# W025A.net
KiCad netlist of a schematic drawn in EAGLE
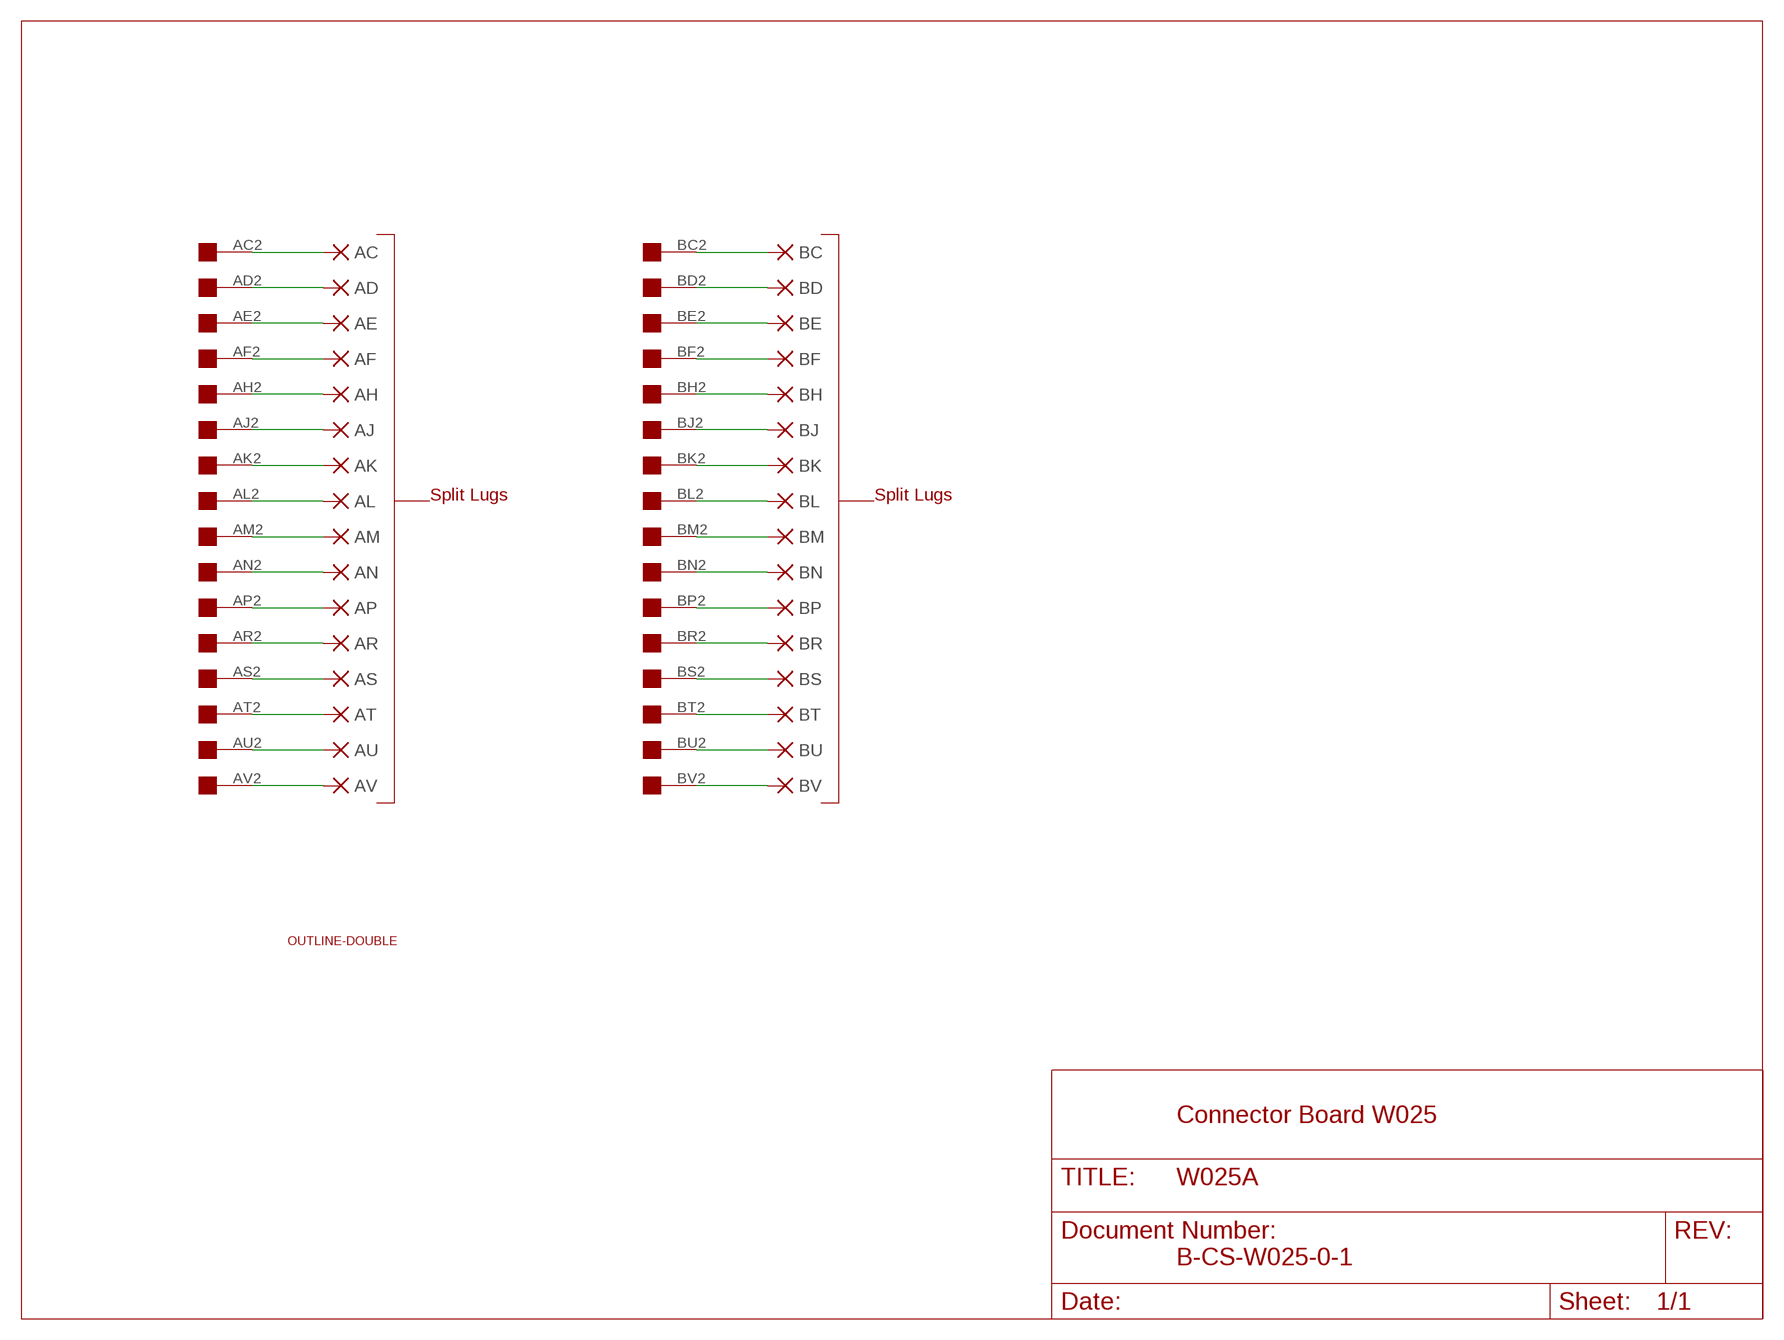
[diagram p0: schematic, sheet 1]

(export (version "E")
  (design (tool "Eeschema 10.0.6"))
  (components
    (comp (ref "AC")
      (value "PAD-0465")
      (footprint "eagle-import:0465")
      (libsource (lib "eagle-import") (part "PAD-0465"))
    )
    (comp (ref "AD")
      (value "PAD-0465")
      (footprint "eagle-import:0465")
      (libsource (lib "eagle-import") (part "PAD-0465"))
    )
    (comp (ref "AE")
      (value "PAD-0465")
      (footprint "eagle-import:0465")
      (libsource (lib "eagle-import") (part "PAD-0465"))
    )
    (comp (ref "AF")
      (value "PAD-0465")
      (footprint "eagle-import:0465")
      (libsource (lib "eagle-import") (part "PAD-0465"))
    )
    (comp (ref "AH")
      (value "PAD-0465")
      (footprint "eagle-import:0465")
      (libsource (lib "eagle-import") (part "PAD-0465"))
    )
    (comp (ref "AJ")
      (value "PAD-0465")
      (footprint "eagle-import:0465")
      (libsource (lib "eagle-import") (part "PAD-0465"))
    )
    (comp (ref "AK")
      (value "PAD-0465")
      (footprint "eagle-import:0465")
      (libsource (lib "eagle-import") (part "PAD-0465"))
    )
    (comp (ref "AL")
      (value "PAD-0465")
      (footprint "eagle-import:0465")
      (libsource (lib "eagle-import") (part "PAD-0465"))
    )
    (comp (ref "AM")
      (value "PAD-0465")
      (footprint "eagle-import:0465")
      (libsource (lib "eagle-import") (part "PAD-0465"))
    )
    (comp (ref "AN")
      (value "PAD-0465")
      (footprint "eagle-import:0465")
      (libsource (lib "eagle-import") (part "PAD-0465"))
    )
    (comp (ref "AP")
      (value "PAD-0465")
      (footprint "eagle-import:0465")
      (libsource (lib "eagle-import") (part "PAD-0465"))
    )
    (comp (ref "AR")
      (value "PAD-0465")
      (footprint "eagle-import:0465")
      (libsource (lib "eagle-import") (part "PAD-0465"))
    )
    (comp (ref "AS")
      (value "PAD-0465")
      (footprint "eagle-import:0465")
      (libsource (lib "eagle-import") (part "PAD-0465"))
    )
    (comp (ref "AT")
      (value "PAD-0465")
      (footprint "eagle-import:0465")
      (libsource (lib "eagle-import") (part "PAD-0465"))
    )
    (comp (ref "AU")
      (value "PAD-0465")
      (footprint "eagle-import:0465")
      (libsource (lib "eagle-import") (part "PAD-0465"))
    )
    (comp (ref "AV")
      (value "PAD-0465")
      (footprint "eagle-import:0465")
      (libsource (lib "eagle-import") (part "PAD-0465"))
    )
    (comp (ref "BC")
      (value "PAD-0465")
      (footprint "eagle-import:0465")
      (libsource (lib "eagle-import") (part "PAD-0465"))
    )
    (comp (ref "BD")
      (value "PAD-0465")
      (footprint "eagle-import:0465")
      (libsource (lib "eagle-import") (part "PAD-0465"))
    )
    (comp (ref "BE")
      (value "PAD-0465")
      (footprint "eagle-import:0465")
      (libsource (lib "eagle-import") (part "PAD-0465"))
    )
    (comp (ref "BF")
      (value "PAD-0465")
      (footprint "eagle-import:0465")
      (libsource (lib "eagle-import") (part "PAD-0465"))
    )
    (comp (ref "BH")
      (value "PAD-0465")
      (footprint "eagle-import:0465")
      (libsource (lib "eagle-import") (part "PAD-0465"))
    )
    (comp (ref "BJ")
      (value "PAD-0465")
      (footprint "eagle-import:0465")
      (libsource (lib "eagle-import") (part "PAD-0465"))
    )
    (comp (ref "BK")
      (value "PAD-0465")
      (footprint "eagle-import:0465")
      (libsource (lib "eagle-import") (part "PAD-0465"))
    )
    (comp (ref "BL")
      (value "PAD-0465")
      (footprint "eagle-import:0465")
      (libsource (lib "eagle-import") (part "PAD-0465"))
    )
    (comp (ref "BM")
      (value "PAD-0465")
      (footprint "eagle-import:0465")
      (libsource (lib "eagle-import") (part "PAD-0465"))
    )
    (comp (ref "BN")
      (value "PAD-0465")
      (footprint "eagle-import:0465")
      (libsource (lib "eagle-import") (part "PAD-0465"))
    )
    (comp (ref "BP")
      (value "PAD-0465")
      (footprint "eagle-import:0465")
      (libsource (lib "eagle-import") (part "PAD-0465"))
    )
    (comp (ref "BR")
      (value "PAD-0465")
      (footprint "eagle-import:0465")
      (libsource (lib "eagle-import") (part "PAD-0465"))
    )
    (comp (ref "BS")
      (value "PAD-0465")
      (footprint "eagle-import:0465")
      (libsource (lib "eagle-import") (part "PAD-0465"))
    )
    (comp (ref "BT")
      (value "PAD-0465")
      (footprint "eagle-import:0465")
      (libsource (lib "eagle-import") (part "PAD-0465"))
    )
    (comp (ref "BU")
      (value "PAD-0465")
      (footprint "eagle-import:0465")
      (libsource (lib "eagle-import") (part "PAD-0465"))
    )
    (comp (ref "BV")
      (value "PAD-0465")
      (footprint "eagle-import:0465")
      (libsource (lib "eagle-import") (part "PAD-0465"))
    )
    (comp (ref "U$1")
      (value "OUTLINE-DOUBLE")
      (footprint "eagle-import:DOUBLE")
      (libsource (lib "eagle-import") (part "OUTLINE-DOUBLE"))
    )
    (comp (ref "U$3")
      (value "DOUBLE")
      (footprint "eagle-import:EDGE-CON4")
      (libsource (lib "eagle-import") (part "DOUBLE"))
    )
  )
  (nets
    (net (code "1") (name "Net-(AC-P)") (class "Default")
      (node (ref "AC") (pin "P$1") (pinfunction "P_P$1") (pintype "passive"))
      (node (ref "U$3") (pin "AC2") (pinfunction "1_AC2") (pintype "bidirectional"))
    )
    (net (code "2") (name "Net-(AD-P)") (class "Default")
      (node (ref "AD") (pin "P$1") (pinfunction "P_P$1") (pintype "passive"))
      (node (ref "U$3") (pin "AD2") (pinfunction "1_AD2") (pintype "bidirectional"))
    )
    (net (code "3") (name "Net-(AE-P)") (class "Default")
      (node (ref "AE") (pin "P$1") (pinfunction "P_P$1") (pintype "passive"))
      (node (ref "U$3") (pin "AE2") (pinfunction "1_AE2") (pintype "bidirectional"))
    )
    (net (code "4") (name "Net-(AF-P)") (class "Default")
      (node (ref "AF") (pin "P$1") (pinfunction "P_P$1") (pintype "passive"))
      (node (ref "U$3") (pin "AF2") (pinfunction "1_AF2") (pintype "bidirectional"))
    )
    (net (code "5") (name "Net-(AH-P)") (class "Default")
      (node (ref "AH") (pin "P$1") (pinfunction "P_P$1") (pintype "passive"))
      (node (ref "U$3") (pin "AH2") (pinfunction "1_AH2") (pintype "bidirectional"))
    )
    (net (code "6") (name "Net-(AJ-P)") (class "Default")
      (node (ref "AJ") (pin "P$1") (pinfunction "P_P$1") (pintype "passive"))
      (node (ref "U$3") (pin "AJ2") (pinfunction "1_AJ2") (pintype "bidirectional"))
    )
    (net (code "7") (name "Net-(AK-P)") (class "Default")
      (node (ref "AK") (pin "P$1") (pinfunction "P_P$1") (pintype "passive"))
      (node (ref "U$3") (pin "AK2") (pinfunction "1_AK2") (pintype "bidirectional"))
    )
    (net (code "8") (name "Net-(AL-P)") (class "Default")
      (node (ref "AL") (pin "P$1") (pinfunction "P_P$1") (pintype "passive"))
      (node (ref "U$3") (pin "AL2") (pinfunction "1_AL2") (pintype "bidirectional"))
    )
    (net (code "9") (name "Net-(AM-P)") (class "Default")
      (node (ref "AM") (pin "P$1") (pinfunction "P_P$1") (pintype "passive"))
      (node (ref "U$3") (pin "AM2") (pinfunction "1_AM2") (pintype "bidirectional"))
    )
    (net (code "10") (name "Net-(AN-P)") (class "Default")
      (node (ref "AN") (pin "P$1") (pinfunction "P_P$1") (pintype "passive"))
      (node (ref "U$3") (pin "AN2") (pinfunction "1_AN2") (pintype "bidirectional"))
    )
    (net (code "11") (name "Net-(AP-P)") (class "Default")
      (node (ref "AP") (pin "P$1") (pinfunction "P_P$1") (pintype "passive"))
      (node (ref "U$3") (pin "AP2") (pinfunction "1_AP2") (pintype "bidirectional"))
    )
    (net (code "12") (name "Net-(AR-P)") (class "Default")
      (node (ref "AR") (pin "P$1") (pinfunction "P_P$1") (pintype "passive"))
      (node (ref "U$3") (pin "AR2") (pinfunction "1_AR2") (pintype "bidirectional"))
    )
    (net (code "13") (name "Net-(AS-P)") (class "Default")
      (node (ref "AS") (pin "P$1") (pinfunction "P_P$1") (pintype "passive"))
      (node (ref "U$3") (pin "AS2") (pinfunction "1_AS2") (pintype "bidirectional"))
    )
    (net (code "14") (name "Net-(AT-P)") (class "Default")
      (node (ref "AT") (pin "P$1") (pinfunction "P_P$1") (pintype "passive"))
      (node (ref "U$3") (pin "AT2") (pinfunction "1_AT2") (pintype "bidirectional"))
    )
    (net (code "15") (name "Net-(AU-P)") (class "Default")
      (node (ref "AU") (pin "P$1") (pinfunction "P_P$1") (pintype "passive"))
      (node (ref "U$3") (pin "AU2") (pinfunction "1_AU2") (pintype "bidirectional"))
    )
    (net (code "16") (name "Net-(AV-P)") (class "Default")
      (node (ref "AV") (pin "P$1") (pinfunction "P_P$1") (pintype "passive"))
      (node (ref "U$3") (pin "AV2") (pinfunction "1_AV2") (pintype "bidirectional"))
    )
    (net (code "17") (name "Net-(BC-P)") (class "Default")
      (node (ref "BC") (pin "P$1") (pinfunction "P_P$1") (pintype "passive"))
      (node (ref "U$3") (pin "BC2") (pinfunction "1_BC2") (pintype "bidirectional"))
    )
    (net (code "18") (name "Net-(BD-P)") (class "Default")
      (node (ref "BD") (pin "P$1") (pinfunction "P_P$1") (pintype "passive"))
      (node (ref "U$3") (pin "BD2") (pinfunction "1_BD2") (pintype "bidirectional"))
    )
    (net (code "19") (name "Net-(BE-P)") (class "Default")
      (node (ref "BE") (pin "P$1") (pinfunction "P_P$1") (pintype "passive"))
      (node (ref "U$3") (pin "BE2") (pinfunction "1_BE2") (pintype "bidirectional"))
    )
    (net (code "20") (name "Net-(BF-P)") (class "Default")
      (node (ref "BF") (pin "P$1") (pinfunction "P_P$1") (pintype "passive"))
      (node (ref "U$3") (pin "BF2") (pinfunction "1_BF2") (pintype "bidirectional"))
    )
    (net (code "21") (name "Net-(BH-P)") (class "Default")
      (node (ref "BH") (pin "P$1") (pinfunction "P_P$1") (pintype "passive"))
      (node (ref "U$3") (pin "BH2") (pinfunction "1_BH2") (pintype "bidirectional"))
    )
    (net (code "22") (name "Net-(BJ-P)") (class "Default")
      (node (ref "BJ") (pin "P$1") (pinfunction "P_P$1") (pintype "passive"))
      (node (ref "U$3") (pin "BJ2") (pinfunction "1_BJ2") (pintype "bidirectional"))
    )
    (net (code "23") (name "Net-(BK-P)") (class "Default")
      (node (ref "BK") (pin "P$1") (pinfunction "P_P$1") (pintype "passive"))
      (node (ref "U$3") (pin "BK2") (pinfunction "1_BK2") (pintype "bidirectional"))
    )
    (net (code "24") (name "Net-(BL-P)") (class "Default")
      (node (ref "BL") (pin "P$1") (pinfunction "P_P$1") (pintype "passive"))
      (node (ref "U$3") (pin "BL2") (pinfunction "1_BL2") (pintype "bidirectional"))
    )
    (net (code "25") (name "Net-(BM-P)") (class "Default")
      (node (ref "BM") (pin "P$1") (pinfunction "P_P$1") (pintype "passive"))
      (node (ref "U$3") (pin "BM2") (pinfunction "1_BM2") (pintype "bidirectional"))
    )
    (net (code "26") (name "Net-(BN-P)") (class "Default")
      (node (ref "BN") (pin "P$1") (pinfunction "P_P$1") (pintype "passive"))
      (node (ref "U$3") (pin "BN2") (pinfunction "1_BN2") (pintype "bidirectional"))
    )
    (net (code "27") (name "Net-(BP-P)") (class "Default")
      (node (ref "BP") (pin "P$1") (pinfunction "P_P$1") (pintype "passive"))
      (node (ref "U$3") (pin "BP2") (pinfunction "1_BP2") (pintype "bidirectional"))
    )
    (net (code "28") (name "Net-(BR-P)") (class "Default")
      (node (ref "BR") (pin "P$1") (pinfunction "P_P$1") (pintype "passive"))
      (node (ref "U$3") (pin "BR2") (pinfunction "1_BR2") (pintype "bidirectional"))
    )
    (net (code "29") (name "Net-(BS-P)") (class "Default")
      (node (ref "BS") (pin "P$1") (pinfunction "P_P$1") (pintype "passive"))
      (node (ref "U$3") (pin "BS2") (pinfunction "1_BS2") (pintype "bidirectional"))
    )
    (net (code "30") (name "Net-(BT-P)") (class "Default")
      (node (ref "BT") (pin "P$1") (pinfunction "P_P$1") (pintype "passive"))
      (node (ref "U$3") (pin "BT2") (pinfunction "1_BT2") (pintype "bidirectional"))
    )
    (net (code "31") (name "Net-(BU-P)") (class "Default")
      (node (ref "BU") (pin "P$1") (pinfunction "P_P$1") (pintype "passive"))
      (node (ref "U$3") (pin "BU2") (pinfunction "1_BU2") (pintype "bidirectional"))
    )
    (net (code "32") (name "Net-(BV-P)") (class "Default")
      (node (ref "BV") (pin "P$1") (pinfunction "P_P$1") (pintype "passive"))
      (node (ref "U$3") (pin "BV2") (pinfunction "1_BV2") (pintype "bidirectional"))
    )
  )
)
